# 5vac-dcreg.net
KiCad netlist of a schematic drawn in EAGLE
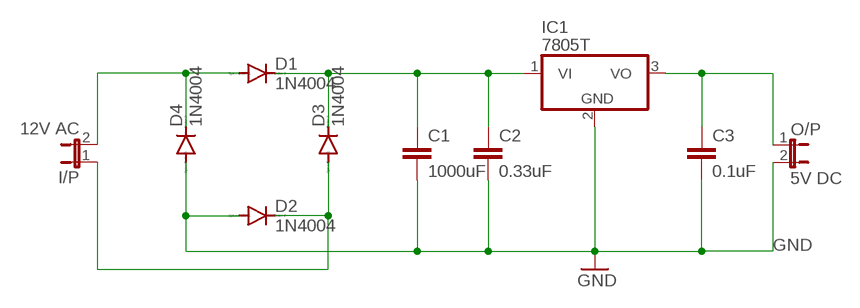
[diagram p0: schematic, sheet 1]

(export (version "E")
  (design (tool "Eeschema 10.0.6"))
  (components
    (comp (ref "C1")
      (value "1000uF")
      (footprint "eagle-import:C2.5-3")
      (libsource (lib "eagle-import") (part "C2,5-3"))
    )
    (comp (ref "C2")
      (value "0.33uF")
      (footprint "eagle-import:C2.5-3")
      (libsource (lib "eagle-import") (part "C2,5-3"))
    )
    (comp (ref "C3")
      (value "0.1uF")
      (footprint "eagle-import:C2.5-3")
      (libsource (lib "eagle-import") (part "C2,5-3"))
    )
    (comp (ref "D1")
      (value "1N4004")
      (footprint "eagle-import:DO41-10")
      (libsource (lib "eagle-import") (part "1N4004"))
    )
    (comp (ref "D2")
      (value "1N4004")
      (footprint "eagle-import:DO41-10")
      (libsource (lib "eagle-import") (part "1N4004"))
    )
    (comp (ref "D3")
      (value "1N4004")
      (footprint "eagle-import:DO41-10")
      (libsource (lib "eagle-import") (part "1N4004"))
    )
    (comp (ref "D4")
      (value "1N4004")
      (footprint "eagle-import:DO41-10")
      (libsource (lib "eagle-import") (part "1N4004"))
    )
    (comp (ref "I/P")
      (value "12V AC")
      (footprint "eagle-import:JP1")
      (libsource (lib "eagle-import") (part "JP1E"))
    )
    (comp (ref "IC1")
      (value "7805T")
      (footprint "eagle-import:TO220H")
      (libsource (lib "eagle-import") (part "78T05"))
    )
    (comp (ref "O/P")
      (value "5V DC")
      (footprint "eagle-import:JP1")
      (libsource (lib "eagle-import") (part "JP1E"))
    )
  )
  (nets
    (net (code "1") (name "GND") (class "Default")
      (node (ref "C1") (pin "2") (pinfunction "2_2") (pintype "passive"))
      (node (ref "C2") (pin "2") (pinfunction "2_2") (pintype "passive"))
      (node (ref "C3") (pin "2") (pinfunction "2_2") (pintype "passive"))
      (node (ref "D2") (pin "A") (pinfunction "A_A") (pintype "passive"))
      (node (ref "D4") (pin "A") (pinfunction "A_A") (pintype "passive"))
      (node (ref "IC1") (pin "2") (pinfunction "GND_2") (pintype "passive"))
      (node (ref "O/P") (pin "2") (pinfunction "2_2") (pintype "passive"))
    )
    (net (code "2") (name "Net-(D1-PadA)") (class "Default")
      (node (ref "D1") (pin "A") (pinfunction "A_A") (pintype "passive"))
      (node (ref "D4") (pin "C") (pinfunction "C_C") (pintype "passive"))
      (node (ref "I/P") (pin "2") (pinfunction "2_2") (pintype "passive"))
    )
    (net (code "3") (name "Net-(D2-PadC)") (class "Default")
      (node (ref "D2") (pin "C") (pinfunction "C_C") (pintype "passive"))
      (node (ref "D3") (pin "A") (pinfunction "A_A") (pintype "passive"))
      (node (ref "I/P") (pin "1") (pinfunction "1_1") (pintype "passive"))
    )
    (net (code "4") (name "Net-(IC1-VI)") (class "Default")
      (node (ref "C1") (pin "1") (pinfunction "1_1") (pintype "passive"))
      (node (ref "C2") (pin "1") (pinfunction "1_1") (pintype "passive"))
      (node (ref "D1") (pin "C") (pinfunction "C_C") (pintype "passive"))
      (node (ref "D3") (pin "C") (pinfunction "C_C") (pintype "passive"))
      (node (ref "IC1") (pin "1") (pinfunction "VI_1") (pintype "input"))
    )
    (net (code "5") (name "Net-(IC1-VO)") (class "Default")
      (node (ref "C3") (pin "1") (pinfunction "1_1") (pintype "passive"))
      (node (ref "IC1") (pin "3") (pinfunction "VO_3") (pintype "passive"))
      (node (ref "O/P") (pin "1") (pinfunction "1_1") (pintype "passive"))
    )
  )
)
